# SparkFun_ESP32_Thing_Plus_DMX_to_LED_Shi.net
KiCad netlist of a schematic drawn in EAGLE
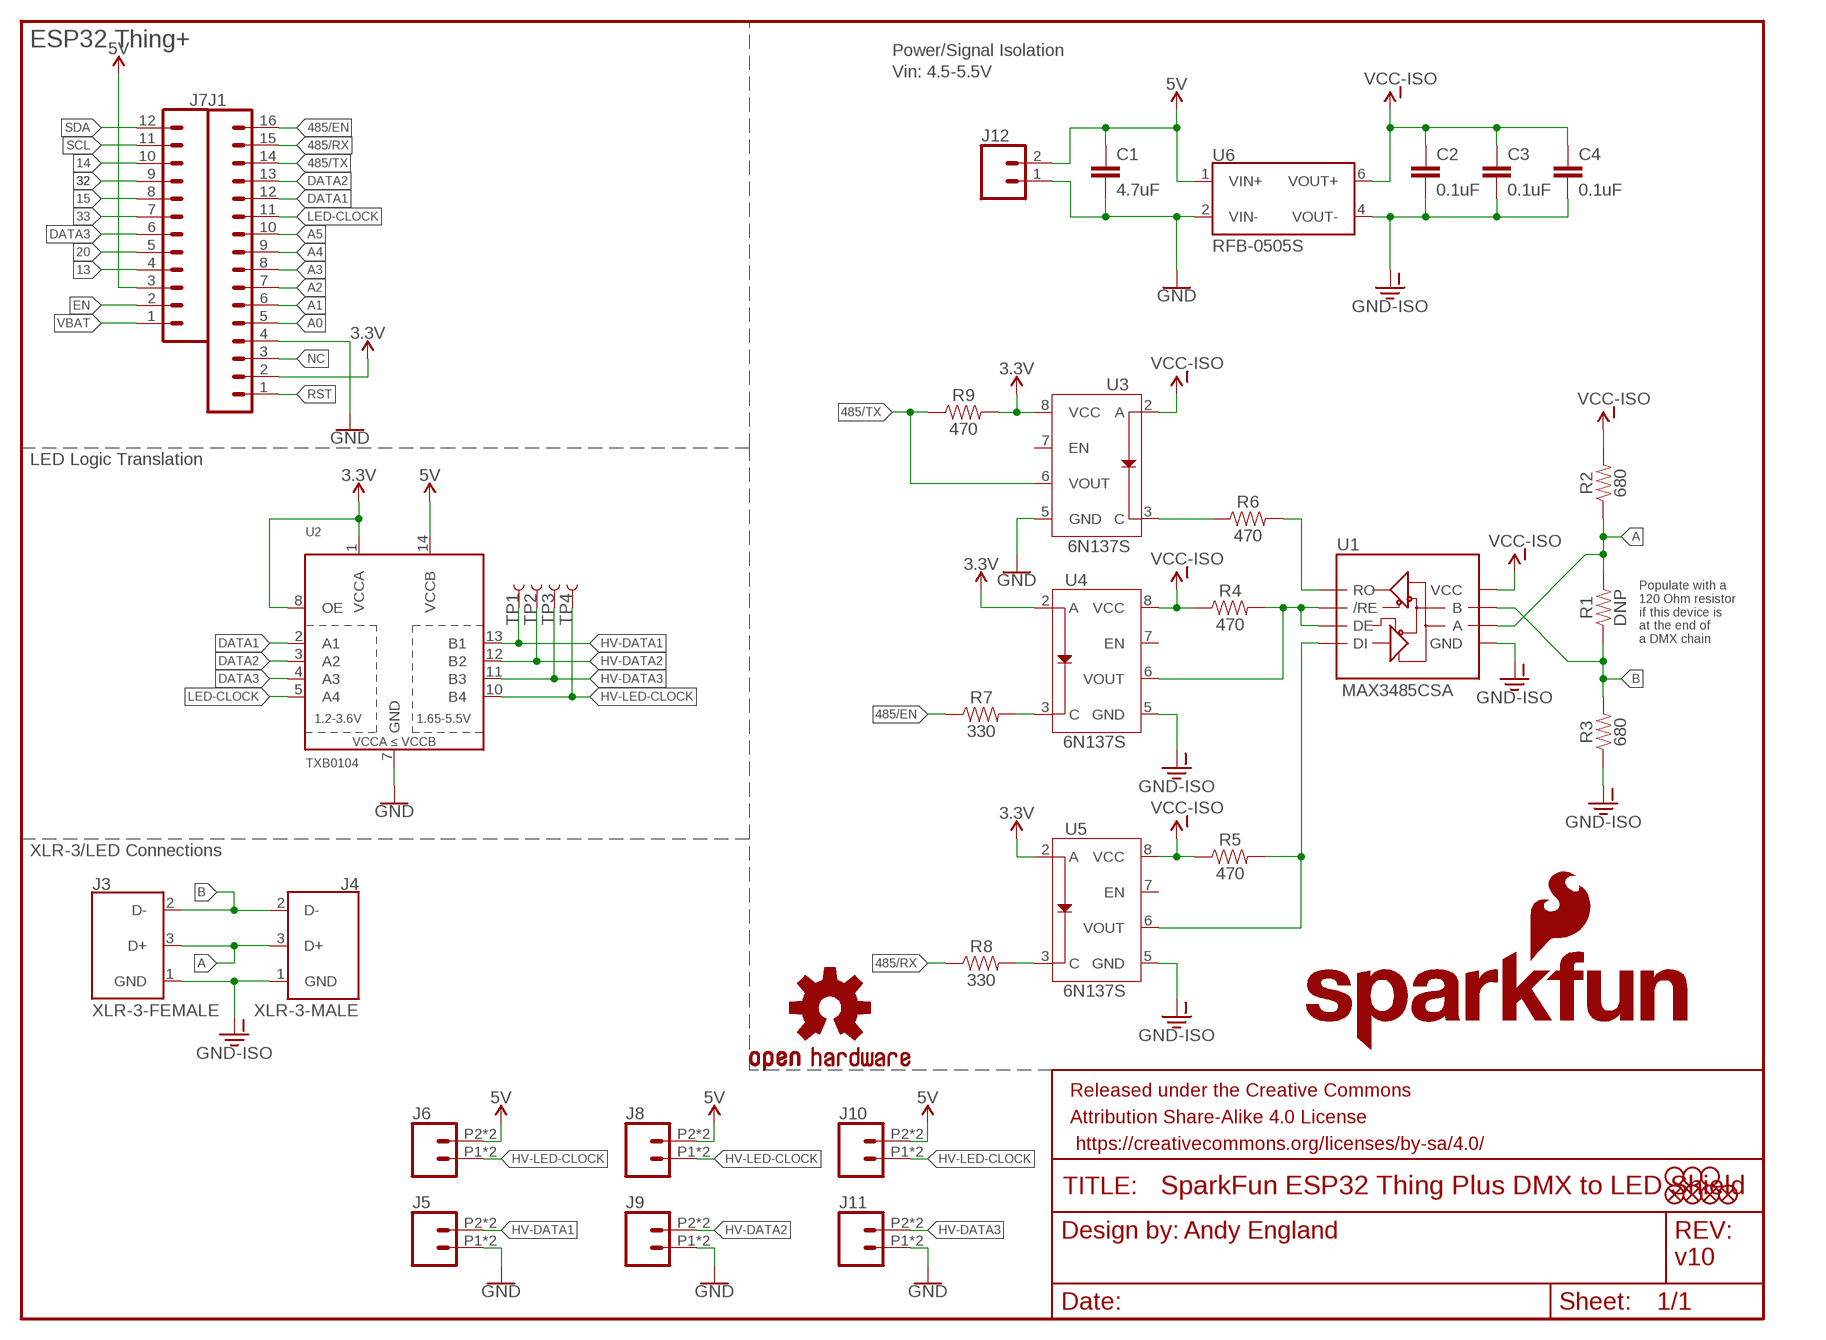
[diagram p0: schematic, sheet 1]

(export (version "E")
  (design (tool "Eeschema 10.0.6"))
  (components
    (comp (ref "C1")
      (value "4.7uF")
      (footprint "eagle-import:0603")
      (libsource (lib "eagle-import") (part "4.7UF-0603-6.3V-(10%)"))
    )
    (comp (ref "C2")
      (value "0.1uF")
      (footprint "eagle-import:0603")
      (libsource (lib "eagle-import") (part "0.1UF-0603-25V-(+80/-20%)"))
    )
    (comp (ref "C3")
      (value "0.1uF")
      (footprint "eagle-import:0603")
      (libsource (lib "eagle-import") (part "0.1UF-0603-25V-(+80/-20%)"))
    )
    (comp (ref "C4")
      (value "0.1uF")
      (footprint "eagle-import:0603")
      (libsource (lib "eagle-import") (part "0.1UF-0603-25V-(+80/-20%)"))
    )
    (comp (ref "FD1")
      (value "FIDUCIALUFIDUCIAL")
      (footprint "eagle-import:FIDUCIAL-MICRO")
      (libsource (lib "eagle-import") (part "FIDUCIALUFIDUCIAL"))
    )
    (comp (ref "FD2")
      (value "FIDUCIALUFIDUCIAL")
      (footprint "eagle-import:FIDUCIAL-MICRO")
      (libsource (lib "eagle-import") (part "FIDUCIALUFIDUCIAL"))
    )
    (comp (ref "FD3")
      (value "FIDUCIALUFIDUCIAL")
      (footprint "eagle-import:FIDUCIAL-MICRO")
      (libsource (lib "eagle-import") (part "FIDUCIALUFIDUCIAL"))
    )
    (comp (ref "FD4")
      (value "FIDUCIALUFIDUCIAL")
      (footprint "eagle-import:FIDUCIAL-MICRO")
      (libsource (lib "eagle-import") (part "FIDUCIALUFIDUCIAL"))
    )
    (comp (ref "FRAME1")
      (value "FRAME-LETTER")
      (footprint "eagle-import:CREATIVE_COMMONS")
      (libsource (lib "eagle-import") (part "FRAME-LETTER"))
    )
    (comp (ref "H1")
      (value "STAND-OFFTIGHT")
      (footprint "eagle-import:STAND-OFF-TIGHT")
      (libsource (lib "eagle-import") (part "STAND-OFFTIGHT"))
    )
    (comp (ref "H2")
      (value "STAND-OFFTIGHT")
      (footprint "eagle-import:STAND-OFF-TIGHT")
      (libsource (lib "eagle-import") (part "STAND-OFFTIGHT"))
    )
    (comp (ref "H3")
      (value "STAND-OFFTIGHT")
      (footprint "eagle-import:STAND-OFF-TIGHT")
      (libsource (lib "eagle-import") (part "STAND-OFFTIGHT"))
    )
    (comp (ref "J1")
      (value "CONN_16LOCK_NO_SILK")
      (footprint "eagle-import:1X16_LOCK_NO_SILK")
      (libsource (lib "eagle-import") (part "CONN_16LOCK_NO_SILK"))
    )
    (comp (ref "J3")
      (value "XLR-3-FEMALE")
      (footprint "eagle-import:XLR-3_FEMALE")
      (libsource (lib "eagle-import") (part "XLR-3-FEMALE"))
    )
    (comp (ref "J4")
      (value "XLR-3-MALE")
      (footprint "eagle-import:XLR-3_MALE")
      (libsource (lib "eagle-import") (part "XLR-3-MALE"))
    )
    (comp (ref "J5")
      (value "CONN_02SMALL_POKEHOME")
      (footprint "eagle-import:1X02_POKEHOME")
      (libsource (lib "eagle-import") (part "CONN_02SMALL_POKEHOME"))
    )
    (comp (ref "J6")
      (value "CONN_02SMALL_POKEHOME")
      (footprint "eagle-import:1X02_POKEHOME")
      (libsource (lib "eagle-import") (part "CONN_02SMALL_POKEHOME"))
    )
    (comp (ref "J7")
      (value "CONN_12LOCK_NO_SILK")
      (footprint "eagle-import:1X12_LOCK_NO_SILK")
      (libsource (lib "eagle-import") (part "CONN_12LOCK_NO_SILK"))
    )
    (comp (ref "J8")
      (value "CONN_02SMALL_POKEHOME")
      (footprint "eagle-import:1X02_POKEHOME")
      (libsource (lib "eagle-import") (part "CONN_02SMALL_POKEHOME"))
    )
    (comp (ref "J9")
      (value "CONN_02SMALL_POKEHOME")
      (footprint "eagle-import:1X02_POKEHOME")
      (libsource (lib "eagle-import") (part "CONN_02SMALL_POKEHOME"))
    )
    (comp (ref "J10")
      (value "CONN_02SMALL_POKEHOME")
      (footprint "eagle-import:1X02_POKEHOME")
      (libsource (lib "eagle-import") (part "CONN_02SMALL_POKEHOME"))
    )
    (comp (ref "J11")
      (value "CONN_02SMALL_POKEHOME")
      (footprint "eagle-import:1X02_POKEHOME")
      (libsource (lib "eagle-import") (part "CONN_02SMALL_POKEHOME"))
    )
    (comp (ref "J12")
      (value "CONN_023.5MM")
      (footprint "eagle-import:SCREWTERMINAL-3.5MM-2")
      (libsource (lib "eagle-import") (part "CONN_023.5MM"))
    )
    (comp (ref "LOGO1")
      (value "SFE_LOGO_NAME_FLAME.2_INCH")
      (footprint "eagle-import:SFE_LOGO_NAME_FLAME_.2")
      (libsource (lib "eagle-import") (part "SFE_LOGO_NAME_FLAME.2_INCH"))
    )
    (comp (ref "LOGO2")
      (value "SFE_LOGO_NAME_FLAME.2_INCH")
      (footprint "eagle-import:SFE_LOGO_NAME_FLAME_.2")
      (libsource (lib "eagle-import") (part "SFE_LOGO_NAME_FLAME.2_INCH"))
    )
    (comp (ref "LOGO3")
      (value "OSHW-LOGOS")
      (footprint "eagle-import:OSHW-LOGO-S")
      (libsource (lib "eagle-import") (part "OSHW-LOGOS"))
    )
    (comp (ref "R1")
      (value "DNP")
      (footprint "eagle-import:AXIAL-0.3EZ")
      (libsource (lib "eagle-import") (part "100OHM-HORIZ_KIT-1/4W-1%"))
    )
    (comp (ref "R2")
      (value "680")
      (footprint "eagle-import:0603")
      (libsource (lib "eagle-import") (part "680OHM-0603-1/10W-5%"))
    )
    (comp (ref "R3")
      (value "680")
      (footprint "eagle-import:0603")
      (libsource (lib "eagle-import") (part "680OHM-0603-1/10W-5%"))
    )
    (comp (ref "R4")
      (value "470")
      (footprint "eagle-import:0603")
      (libsource (lib "eagle-import") (part "470OHM-0603-1/10W-1%"))
    )
    (comp (ref "R5")
      (value "470")
      (footprint "eagle-import:0603")
      (libsource (lib "eagle-import") (part "470OHM-0603-1/10W-1%"))
    )
    (comp (ref "R6")
      (value "470")
      (footprint "eagle-import:0603")
      (libsource (lib "eagle-import") (part "470OHM-0603-1/10W-1%"))
    )
    (comp (ref "R7")
      (value "330")
      (footprint "eagle-import:0603")
      (libsource (lib "eagle-import") (part "330OHM-0603-1/10W-1%"))
    )
    (comp (ref "R8")
      (value "330")
      (footprint "eagle-import:0603")
      (libsource (lib "eagle-import") (part "330OHM-0603-1/10W-1%"))
    )
    (comp (ref "R9")
      (value "470")
      (footprint "eagle-import:0603")
      (libsource (lib "eagle-import") (part "470OHM-0603-1/10W-1%"))
    )
    (comp (ref "TP1")
      (value "TEST-POINT3")
      (footprint "eagle-import:PAD.03X.03")
      (libsource (lib "eagle-import") (part "TEST-POINT3"))
    )
    (comp (ref "TP2")
      (value "TEST-POINT3")
      (footprint "eagle-import:PAD.03X.03")
      (libsource (lib "eagle-import") (part "TEST-POINT3"))
    )
    (comp (ref "TP3")
      (value "TEST-POINT3")
      (footprint "eagle-import:PAD.03X.03")
      (libsource (lib "eagle-import") (part "TEST-POINT3"))
    )
    (comp (ref "TP4")
      (value "TEST-POINT3")
      (footprint "eagle-import:PAD.03X.03")
      (libsource (lib "eagle-import") (part "TEST-POINT3"))
    )
    (comp (ref "U1")
      (value "MAX3485CSA")
      (footprint "eagle-import:SO08")
      (libsource (lib "eagle-import") (part "RS485SOIC"))
    )
    (comp (ref "U2")
      (value "TXB0104")
      (footprint "eagle-import:TSSOP14")
      (libsource (lib "eagle-import") (part "TXB0104PWR"))
    )
    (comp (ref "U3")
      (value "6N137S")
      (footprint "eagle-import:8-SMD")
      (libsource (lib "eagle-import") (part "6N137S"))
    )
    (comp (ref "U4")
      (value "6N137S")
      (footprint "eagle-import:8-SMD")
      (libsource (lib "eagle-import") (part "6N137S"))
    )
    (comp (ref "U5")
      (value "6N137S")
      (footprint "eagle-import:8-SMD")
      (libsource (lib "eagle-import") (part "6N137S"))
    )
    (comp (ref "U6")
      (value "RFB-0505S")
      (footprint "eagle-import:RFB-0505S")
      (libsource (lib "eagle-import") (part "RFB-0505S"))
    )
  )
  (nets
    (net (code "1") (name "3.3V") (class "Default")
      (node (ref "J1") (pin "2") (pinfunction "2_2") (pintype "passive"))
      (node (ref "R9") (pin "2") (pinfunction "2_2") (pintype "passive"))
      (node (ref "U2") (pin "1") (pinfunction "VCCA_1") (pintype "bidirectional"))
      (node (ref "U2") (pin "8") (pinfunction "OE_8") (pintype "bidirectional"))
      (node (ref "U3") (pin "8") (pinfunction "VCC_8") (pintype "bidirectional"))
      (node (ref "U4") (pin "2") (pinfunction "A_2") (pintype "bidirectional"))
      (node (ref "U5") (pin "2") (pinfunction "A_2") (pintype "bidirectional"))
    )
    (net (code "2") (name "5V") (class "Default")
      (node (ref "C1") (pin "1") (pinfunction "1_1") (pintype "passive"))
      (node (ref "J10") (pin "P2") (pinfunction "2_P2") (pintype "passive"))
      (node (ref "J10") (pin "P4") (pinfunction "2_P4") (pintype "passive"))
      (node (ref "J12") (pin "2") (pinfunction "2_2") (pintype "passive"))
      (node (ref "J6") (pin "P2") (pinfunction "2_P2") (pintype "passive"))
      (node (ref "J6") (pin "P4") (pinfunction "2_P4") (pintype "passive"))
      (node (ref "J7") (pin "3") (pinfunction "3_3") (pintype "passive"))
      (node (ref "J8") (pin "P2") (pinfunction "2_P2") (pintype "passive"))
      (node (ref "J8") (pin "P4") (pinfunction "2_P4") (pintype "passive"))
      (node (ref "U2") (pin "14") (pinfunction "VCCB_14") (pintype "bidirectional"))
      (node (ref "U6") (pin "1") (pinfunction "VIN+_1") (pintype "bidirectional"))
    )
    (net (code "3") (name "13") (class "Default")
      (node (ref "J7") (pin "4") (pinfunction "4_4") (pintype "passive"))
    )
    (net (code "4") (name "14") (class "Default")
      (node (ref "J7") (pin "10") (pinfunction "10_10") (pintype "passive"))
    )
    (net (code "5") (name "15") (class "Default")
      (node (ref "J7") (pin "8") (pinfunction "8_8") (pintype "passive"))
    )
    (net (code "6") (name "20") (class "Default")
      (node (ref "J7") (pin "5") (pinfunction "5_5") (pintype "passive"))
    )
    (net (code "7") (name "32") (class "Default")
      (node (ref "J7") (pin "9") (pinfunction "9_9") (pintype "passive"))
    )
    (net (code "8") (name "33") (class "Default")
      (node (ref "J7") (pin "7") (pinfunction "7_7") (pintype "passive"))
    )
    (net (code "9") (name "485{slash}EN") (class "Default")
      (node (ref "J1") (pin "16") (pinfunction "16_16") (pintype "passive"))
      (node (ref "R7") (pin "1") (pinfunction "1_1") (pintype "passive"))
    )
    (net (code "10") (name "485{slash}RX") (class "Default")
      (node (ref "J1") (pin "15") (pinfunction "15_15") (pintype "passive"))
      (node (ref "R8") (pin "1") (pinfunction "1_1") (pintype "passive"))
    )
    (net (code "11") (name "485{slash}TX") (class "Default")
      (node (ref "J1") (pin "14") (pinfunction "14_14") (pintype "passive"))
      (node (ref "R9") (pin "1") (pinfunction "1_1") (pintype "passive"))
      (node (ref "U3") (pin "6") (pinfunction "VOUT_6") (pintype "bidirectional"))
    )
    (net (code "12") (name "A") (class "Default")
      (node (ref "J3") (pin "3") (pinfunction "D+_3") (pintype "bidirectional"))
      (node (ref "J4") (pin "3") (pinfunction "D+_3") (pintype "bidirectional"))
      (node (ref "R1") (pin "P$2") (pinfunction "2_P$2") (pintype "passive"))
      (node (ref "R2") (pin "1") (pinfunction "1_1") (pintype "passive"))
      (node (ref "U1") (pin "6") (pinfunction "A_6") (pintype "bidirectional"))
    )
    (net (code "13") (name "A0") (class "Default")
      (node (ref "J1") (pin "5") (pinfunction "5_5") (pintype "passive"))
    )
    (net (code "14") (name "A1") (class "Default")
      (node (ref "J1") (pin "6") (pinfunction "6_6") (pintype "passive"))
    )
    (net (code "15") (name "A2") (class "Default")
      (node (ref "J1") (pin "7") (pinfunction "7_7") (pintype "passive"))
    )
    (net (code "16") (name "A3") (class "Default")
      (node (ref "J1") (pin "8") (pinfunction "8_8") (pintype "passive"))
    )
    (net (code "17") (name "A4") (class "Default")
      (node (ref "J1") (pin "9") (pinfunction "9_9") (pintype "passive"))
    )
    (net (code "18") (name "A5") (class "Default")
      (node (ref "J1") (pin "10") (pinfunction "10_10") (pintype "passive"))
    )
    (net (code "19") (name "B") (class "Default")
      (node (ref "J3") (pin "2") (pinfunction "D-_2") (pintype "bidirectional"))
      (node (ref "J4") (pin "2") (pinfunction "D-_2") (pintype "bidirectional"))
      (node (ref "R1") (pin "P$1") (pinfunction "1_P$1") (pintype "passive"))
      (node (ref "R3") (pin "2") (pinfunction "2_2") (pintype "passive"))
      (node (ref "U1") (pin "7") (pinfunction "B_7") (pintype "bidirectional"))
    )
    (net (code "20") (name "DATA1") (class "Default")
      (node (ref "J1") (pin "12") (pinfunction "12_12") (pintype "passive"))
      (node (ref "U2") (pin "2") (pinfunction "A1_2") (pintype "bidirectional"))
    )
    (net (code "21") (name "DATA2") (class "Default")
      (node (ref "J1") (pin "13") (pinfunction "13_13") (pintype "passive"))
      (node (ref "U2") (pin "3") (pinfunction "A2_3") (pintype "bidirectional"))
    )
    (net (code "22") (name "DATA3") (class "Default")
      (node (ref "J7") (pin "6") (pinfunction "6_6") (pintype "passive"))
      (node (ref "U2") (pin "4") (pinfunction "A3_4") (pintype "bidirectional"))
    )
    (net (code "23") (name "EN") (class "Default")
      (node (ref "J7") (pin "2") (pinfunction "2_2") (pintype "passive"))
    )
    (net (code "24") (name "GND") (class "Default")
      (node (ref "C1") (pin "2") (pinfunction "2_2") (pintype "passive"))
      (node (ref "J1") (pin "4") (pinfunction "4_4") (pintype "passive"))
      (node (ref "J11") (pin "P1") (pinfunction "1_P1") (pintype "passive"))
      (node (ref "J11") (pin "P3") (pinfunction "1_P3") (pintype "passive"))
      (node (ref "J12") (pin "1") (pinfunction "1_1") (pintype "passive"))
      (node (ref "J5") (pin "P1") (pinfunction "1_P1") (pintype "passive"))
      (node (ref "J5") (pin "P3") (pinfunction "1_P3") (pintype "passive"))
      (node (ref "J9") (pin "P1") (pinfunction "1_P1") (pintype "passive"))
      (node (ref "J9") (pin "P3") (pinfunction "1_P3") (pintype "passive"))
      (node (ref "U2") (pin "7") (pinfunction "GND_7") (pintype "bidirectional"))
      (node (ref "U3") (pin "5") (pinfunction "GND_5") (pintype "bidirectional"))
      (node (ref "U6") (pin "2") (pinfunction "VIN-_2") (pintype "bidirectional"))
    )
    (net (code "25") (name "GND-ISO") (class "Default")
      (node (ref "C2") (pin "2") (pinfunction "2_2") (pintype "passive"))
      (node (ref "C3") (pin "2") (pinfunction "2_2") (pintype "passive"))
      (node (ref "C4") (pin "2") (pinfunction "2_2") (pintype "passive"))
      (node (ref "J3") (pin "1") (pinfunction "GND_1") (pintype "bidirectional"))
      (node (ref "J4") (pin "1") (pinfunction "GND_1") (pintype "bidirectional"))
      (node (ref "R3") (pin "1") (pinfunction "1_1") (pintype "passive"))
      (node (ref "U1") (pin "5") (pinfunction "GND_5") (pintype "bidirectional"))
      (node (ref "U4") (pin "5") (pinfunction "GND_5") (pintype "bidirectional"))
      (node (ref "U5") (pin "5") (pinfunction "GND_5") (pintype "bidirectional"))
      (node (ref "U6") (pin "4") (pinfunction "VOUT-_4") (pintype "bidirectional"))
    )
    (net (code "26") (name "HV-DATA1") (class "Default")
      (node (ref "J5") (pin "P2") (pinfunction "2_P2") (pintype "passive"))
      (node (ref "J5") (pin "P4") (pinfunction "2_P4") (pintype "passive"))
      (node (ref "TP1") (pin "P$1") (pinfunction "1_P$1") (pintype "bidirectional"))
      (node (ref "U2") (pin "13") (pinfunction "B1_13") (pintype "bidirectional"))
    )
    (net (code "27") (name "HV-DATA2") (class "Default")
      (node (ref "J9") (pin "P2") (pinfunction "2_P2") (pintype "passive"))
      (node (ref "J9") (pin "P4") (pinfunction "2_P4") (pintype "passive"))
      (node (ref "TP2") (pin "P$1") (pinfunction "1_P$1") (pintype "bidirectional"))
      (node (ref "U2") (pin "12") (pinfunction "B2_12") (pintype "bidirectional"))
    )
    (net (code "28") (name "HV-DATA3") (class "Default")
      (node (ref "J11") (pin "P2") (pinfunction "2_P2") (pintype "passive"))
      (node (ref "J11") (pin "P4") (pinfunction "2_P4") (pintype "passive"))
      (node (ref "TP3") (pin "P$1") (pinfunction "1_P$1") (pintype "bidirectional"))
      (node (ref "U2") (pin "11") (pinfunction "B3_11") (pintype "bidirectional"))
    )
    (net (code "29") (name "HV-LED-CLOCK") (class "Default")
      (node (ref "J10") (pin "P1") (pinfunction "1_P1") (pintype "passive"))
      (node (ref "J10") (pin "P3") (pinfunction "1_P3") (pintype "passive"))
      (node (ref "J6") (pin "P1") (pinfunction "1_P1") (pintype "passive"))
      (node (ref "J6") (pin "P3") (pinfunction "1_P3") (pintype "passive"))
      (node (ref "J8") (pin "P1") (pinfunction "1_P1") (pintype "passive"))
      (node (ref "J8") (pin "P3") (pinfunction "1_P3") (pintype "passive"))
      (node (ref "TP4") (pin "P$1") (pinfunction "1_P$1") (pintype "bidirectional"))
      (node (ref "U2") (pin "10") (pinfunction "B4_10") (pintype "bidirectional"))
    )
    (net (code "30") (name "LED-CLOCK") (class "Default")
      (node (ref "J1") (pin "11") (pinfunction "11_11") (pintype "passive"))
      (node (ref "U2") (pin "5") (pinfunction "A4_5") (pintype "bidirectional"))
    )
    (net (code "31") (name "NC") (class "Default")
      (node (ref "J1") (pin "3") (pinfunction "3_3") (pintype "passive"))
    )
    (net (code "32") (name "Net-(U1-DE)") (class "Default")
      (node (ref "R4") (pin "2") (pinfunction "2_2") (pintype "passive"))
      (node (ref "U1") (pin "2") (pinfunction "/RE_2") (pintype "bidirectional"))
      (node (ref "U1") (pin "3") (pinfunction "DE_3") (pintype "bidirectional"))
      (node (ref "U4") (pin "6") (pinfunction "VOUT_6") (pintype "bidirectional"))
    )
    (net (code "33") (name "Net-(U1-DI)") (class "Default")
      (node (ref "R5") (pin "2") (pinfunction "2_2") (pintype "passive"))
      (node (ref "U1") (pin "4") (pinfunction "DI_4") (pintype "bidirectional"))
      (node (ref "U5") (pin "6") (pinfunction "VOUT_6") (pintype "bidirectional"))
    )
    (net (code "34") (name "Net-(U1-RO)") (class "Default")
      (node (ref "R6") (pin "2") (pinfunction "2_2") (pintype "passive"))
      (node (ref "U1") (pin "1") (pinfunction "RO_1") (pintype "bidirectional"))
    )
    (net (code "35") (name "Net-(U3-C)") (class "Default")
      (node (ref "R6") (pin "1") (pinfunction "1_1") (pintype "passive"))
      (node (ref "U3") (pin "3") (pinfunction "C_3") (pintype "bidirectional"))
    )
    (net (code "36") (name "Net-(U4-C)") (class "Default")
      (node (ref "R7") (pin "2") (pinfunction "2_2") (pintype "passive"))
      (node (ref "U4") (pin "3") (pinfunction "C_3") (pintype "bidirectional"))
    )
    (net (code "37") (name "Net-(U5-C)") (class "Default")
      (node (ref "R8") (pin "2") (pinfunction "2_2") (pintype "passive"))
      (node (ref "U5") (pin "3") (pinfunction "C_3") (pintype "bidirectional"))
    )
    (net (code "38") (name "RST") (class "Default")
      (node (ref "J1") (pin "1") (pinfunction "1_1") (pintype "passive"))
    )
    (net (code "39") (name "SCL") (class "Default")
      (node (ref "J7") (pin "11") (pinfunction "11_11") (pintype "passive"))
    )
    (net (code "40") (name "SDA") (class "Default")
      (node (ref "J7") (pin "12") (pinfunction "12_12") (pintype "passive"))
    )
    (net (code "41") (name "VBAT") (class "Default")
      (node (ref "J7") (pin "1") (pinfunction "1_1") (pintype "passive"))
    )
    (net (code "42") (name "VCC-ISO") (class "Default")
      (node (ref "C2") (pin "1") (pinfunction "1_1") (pintype "passive"))
      (node (ref "C3") (pin "1") (pinfunction "1_1") (pintype "passive"))
      (node (ref "C4") (pin "1") (pinfunction "1_1") (pintype "passive"))
      (node (ref "R2") (pin "2") (pinfunction "2_2") (pintype "passive"))
      (node (ref "R4") (pin "1") (pinfunction "1_1") (pintype "passive"))
      (node (ref "R5") (pin "1") (pinfunction "1_1") (pintype "passive"))
      (node (ref "U1") (pin "8") (pinfunction "VCC_8") (pintype "bidirectional"))
      (node (ref "U3") (pin "2") (pinfunction "A_2") (pintype "bidirectional"))
      (node (ref "U4") (pin "8") (pinfunction "VCC_8") (pintype "bidirectional"))
      (node (ref "U5") (pin "8") (pinfunction "VCC_8") (pintype "bidirectional"))
      (node (ref "U6") (pin "6") (pinfunction "VOUT+_6") (pintype "bidirectional"))
    )
    (net (code "43") (name "unconnected-(U3-EN-Pad7)") (class "Default")
      (node (ref "U3") (pin "7") (pinfunction "EN_7") (pintype "bidirectional"))
    )
    (net (code "44") (name "unconnected-(U4-EN-Pad7)") (class "Default")
      (node (ref "U4") (pin "7") (pinfunction "EN_7") (pintype "bidirectional"))
    )
    (net (code "45") (name "unconnected-(U5-EN-Pad7)") (class "Default")
      (node (ref "U5") (pin "7") (pinfunction "EN_7") (pintype "bidirectional"))
    )
  )
)
